# Gas_Sampler-Vin.net
KiCad netlist of a schematic drawn in Altium Designer
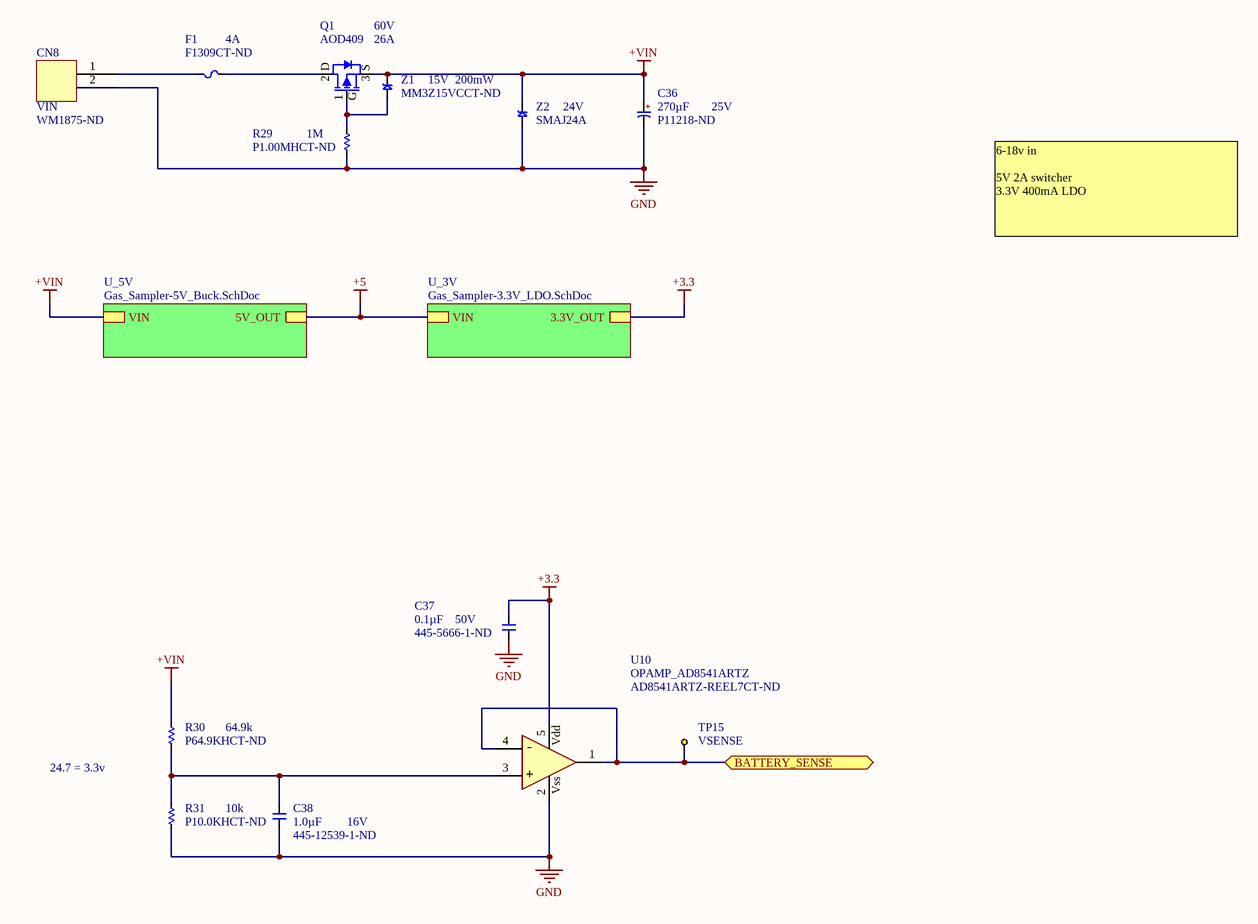
[diagram p0: Gas_Sampler-Vin.SchDoc]

(export (version "E")
  (design (tool "Eeschema 10.0.6"))
  (components
    (comp (ref "C36")
      (value "270µF")
      (footprint "CAP_RADIAL_10MM_DIA_12.5MM_LEN_5MM_LEADSPACE")
      (description "CAP ALUM 270UF 20% 25V RADIAL")
      (fields
        (field (name "MANUFACTURER") "Panasonic Electronic Components")
        (field (name "MANUFACTURER PART NUMBER") "EEU-FC1E271")
        (field (name "VOLTAGE - RATED") "25V")
        (field (name "SUPPLIER PART NUMBER 1") "P11218-ND")
      )
      (libsource (lib "capacitor") (part "CAP_ALUM_270UF_25V_20%_RADIAL_10X12.5MM"))
    )
    (comp (ref "C37")
      (value "0.1µF")
      (footprint "C0603")
      (description "CAP CER 0.1UF 50V 10% X7R 0603")
      (fields
        (field (name "MANUFACTURER") "TDK Corporation")
        (field (name "MANUFACTURER PART NUMBER") "CGA3E2X7R1H104K080AA")
        (field (name "VOLTAGE - RATED") "50V")
        (field (name "SUPPLIER PART NUMBER 1") "445-5666-1-ND")
      )
      (libsource (lib "capacitor") (part "CAP_CER_0603_0.1UF_50V_10%_X7R"))
    )
    (comp (ref "C38")
      (value "1.0µF")
      (footprint "C0603")
      (description "CAP CER 1UF 16V 10% X7R 0603")
      (fields
        (field (name "MANUFACTURER") "TDK Corporation")
        (field (name "MANUFACTURER PART NUMBER") "CGA3E1X7R1C105K080AC")
        (field (name "SUPPLIER PART NUMBER 1") "445-12539-1-ND")
        (field (name "VOLTAGE - RATED") "16V")
      )
      (libsource (lib "capacitor") (part "CAP_CER_0603_1UF_16V_10%_X7R"))
    )
    (comp (ref "CN8")
      (value "VIN")
      (footprint "MICROFIT_3_SINGLE_ROW_RA_TH_CLIP_2POS")
      (description "CONN HEADER 2POS R/A W/CLIP GOLD")
      (fields
        (field (name "MANUFACTURER") "Molex Connector Corporation")
        (field (name "MANUFACTURER PART NUMBER") "43650-0204")
        (field (name "SUPPLIER PART NUMBER 1") "WM1875-ND")
      )
      (libsource (lib "molex micro fit 3") (part "MICROFIT_3_SINGLE_ROW_RA_TH_CLIP_2POS"))
    )
    (comp (ref "F1")
      (value "FUSE_4A_OMNIBLOK_0154004")
      (footprint "FUSEHOLDER_LITTLEFUSE_0154005.DR")
      (description "FUSE Slow 125VAC, 125VDC 4A SMD")
      (fields
        (field (name "MANUFACTURER") "Littelfuse Inc")
        (field (name "MANUFACTURER PART NUMBER") "0154004.DRT")
        (field (name "SUPPLIER PART NUMBER 1") "F1309CT-ND")
        (field (name "CURRENT RATING") "4A")
      )
      (libsource (lib "fuse") (part "FUSE_4A_OMNIBLOK_0154004"))
    )
    (comp (ref "Q1")
      (value "PFET_AOD409")
      (footprint "DPAK")
      (description "MOSFET P-CH -60V -26A TO-252")
      (fields
        (field (name "MANUFACTURER") "Alpha & Omega Semiconductor Inc")
        (field (name "MANUFACTURER PART NUMBER") "AOD409")
        (field (name "DRAIN TO SOURCE VOLTAGE (VDSS)") "60V")
        (field (name "CURRENT - CONTINUOUS DRAIN (ID) @ 25° C") "26A")
      )
      (libsource (lib "transistor_fet") (part "PFET_AOD409"))
    )
    (comp (ref "R29")
      (value "1M")
      (footprint "R0603")
      (description "RES 1M OHM 1/10W 1% 0603 SMD")
      (fields
        (field (name "MANUFACTURER") "Panasonic Electronic Components")
        (field (name "MANUFACTURER PART NUMBER") "ERJ-3EKF1004V")
        (field (name "SUPPLIER PART NUMBER 1") "P1.00MHCT-ND")
      )
      (libsource (lib "resistor") (part "RES_0603_1M_OHM_1/10W_1%"))
    )
    (comp (ref "R30")
      (value "RES_0603_64.9K_OHM_1/10W_1%")
      (footprint "R0603")
      (description "RES 64.9K OHM 1% 1/10W 0603")
      (fields
        (field (name "MANUFACTURER") "Panasonic Electronic Components")
        (field (name "MANUFACTURER PART NUMBER") "ERJ3EKF6492V")
        (field (name "SUPPLIER PART NUMBER 1") "P64.9KHCT-ND")
        (field (name "RESISTANCE (OHMS)") "64.9k")
      )
      (libsource (lib "resistor") (part "RES_0603_64.9K_OHM_1/10W_1%"))
    )
    (comp (ref "R31")
      (value "10k")
      (footprint "R0603")
      (description "RES 10K OHM 1/10W 1% 0603 SMD")
      (fields
        (field (name "MANUFACTURER") "Panasonic Electronic Components")
        (field (name "MANUFACTURER PART NUMBER") "ERJ-3EKF1002V")
        (field (name "SUPPLIER PART NUMBER 1") "P10.0KHCT-ND")
      )
      (libsource (lib "resistor") (part "RES_0603_10K_OHM_1/10W_1%"))
    )
    (comp (ref "TP15")
      (value "VSENSE")
      (footprint "TP_KEYSTONE_5001")
      (description "PC TEST POINT TH RING")
      (fields
        (field (name "MANUFACTURER") "Keystone Electronics")
        (field (name "MANUFACTURER PART NUMBER") "5001")
      )
      (libsource (lib "miscellaneous") (part "TEST_KEYSTONE5001"))
    )
    (comp (ref "U10")
      (value "OPAMP_AD8541ARTZ")
      (footprint "5SOT23")
      (description "IC OPAMP GP R-R CMOS SOT23-5")
      (fields
        (field (name "MANUFACTURER") "Analog Devices Inc")
        (field (name "MANUFACTURER PART NUMBER") "AD8541ARTZ-REEL7")
        (field (name "SUPPLIER PART NUMBER 1") "AD8541ARTZ-REEL7CT-ND")
      )
      (libsource (lib "ic_analog") (part "OPAMP_AD8541ARTZ"))
    )
    (comp (ref "Z1")
      (value "ZENER_MM3Z15VC")
      (footprint "SOD323")
      (description "DIODE ZENER 15V 200MW SOD")
      (fields
        (field (name "MANUFACTURER") "Fairchild Semiconductor")
        (field (name "MANUFACTURER PART NUMBER") "MM3Z15VC")
        (field (name "SUPPLIER PART NUMBER 1") "MM3Z15VCCT-ND")
        (field (name "POWER - MAX") "200mW")
        (field (name "VOLTAGE - ZENER (NOM) (VZ)") "15V")
      )
      (libsource (lib "diode") (part "ZENER_MM3Z15VC"))
    )
    (comp (ref "Z2")
      (value "TVS_UNI_SMAJ24A")
      (footprint "SMA")
      (description "TVS DIODE 24VWM SMD")
      (fields
        (field (name "MANUFACTURER") "Bourns Inc.")
        (field (name "PART NUMBER") "430-00161-00")
        (field (name "VOLTAGE - REVERSE STANDOFF (TYP)") "24V")
        (field (name "MANUFACTURER PART NUMBER") "SMAJ24A")
      )
      (libsource (lib "diode") (part "TVS_UNI_SMAJ24A"))
    )
  )
  (nets
    (net (code "1") (name "+3.3") (class "Default")
      (node (ref "C37") (pin "1") (pintype "passive"))
      (node (ref "U10") (pin "5") (pinfunction "VDD_5") (pintype "passive"))
    )
    (net (code "3") (name "+VIN") (class "Default")
      (node (ref "C36") (pin "1") (pintype "passive"))
      (node (ref "Q1") (pin "3") (pinfunction "S_3") (pintype "passive"))
      (node (ref "R30") (pin "2") (pintype "passive"))
      (node (ref "Z1") (pin "2") (pintype "passive"))
      (node (ref "Z2") (pin "2") (pintype "passive"))
    )
    (net (code "4") (name "/BATTERY_SENSE") (class "Default")
      (node (ref "TP15") (pin "1") (pintype "passive"))
      (node (ref "U10") (pin "1") (pinfunction "OUT_1") (pintype "passive"))
      (node (ref "U10") (pin "4") (pinfunction "IN-_4") (pintype "passive"))
    )
    (net (code "5") (name "GND") (class "Default")
      (node (ref "C36") (pin "2") (pintype "passive"))
      (node (ref "C37") (pin "2") (pintype "passive"))
      (node (ref "C38") (pin "2") (pintype "passive"))
      (node (ref "CN8") (pin "2") (pinfunction "2_2") (pintype "passive"))
      (node (ref "R29") (pin "1") (pintype "passive"))
      (node (ref "R31") (pin "1") (pintype "passive"))
      (node (ref "U10") (pin "2") (pinfunction "VSS_2") (pintype "passive"))
      (node (ref "Z2") (pin "1") (pintype "passive"))
    )
    (net (code "6") (name "Net-(CN8-Pad1)") (class "Default")
      (node (ref "CN8") (pin "1") (pinfunction "1_1") (pintype "passive"))
      (node (ref "F1") (pin "1") (pintype "passive"))
    )
    (net (code "7") (name "Net-(Q1-D)") (class "Default")
      (node (ref "F1") (pin "2") (pintype "passive"))
      (node (ref "Q1") (pin "2") (pinfunction "D_2") (pintype "passive"))
    )
    (net (code "8") (name "Net-(Q1-G)") (class "Default")
      (node (ref "Q1") (pin "1") (pinfunction "G_1") (pintype "passive"))
      (node (ref "R29") (pin "2") (pintype "passive"))
      (node (ref "Z1") (pin "1") (pintype "passive"))
    )
    (net (code "9") (name "Net-(U10-IN+)") (class "Default")
      (node (ref "C38") (pin "1") (pintype "passive"))
      (node (ref "R30") (pin "1") (pintype "passive"))
      (node (ref "R31") (pin "2") (pintype "passive"))
      (node (ref "U10") (pin "3") (pinfunction "IN+_3") (pintype "passive"))
    )
  )
)
